# Master_Transmit.net
KiCad netlist of a schematic drawn in Altium Designer
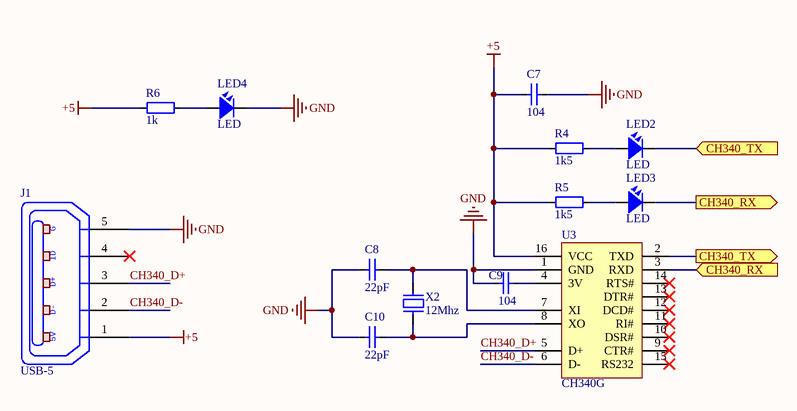
[diagram p0: Master_Transmit.SchDoc]

(export (version "E")
  (design (tool "Eeschema 10.0.6"))
  (components
    (comp (ref "C7")
      (value "104")
      (footprint "CAP_0805")
      (description "Capacitor")
      (fields (field (name "PUBLISHER") "Altium Limited"))
      (libsource (lib "My Library") (part "CapSMD"))
    )
    (comp (ref "C8")
      (value "22pF")
      (footprint "CAP_0805")
      (description "Capacitor")
      (fields (field (name "PUBLISHER") "Altium Limited"))
      (libsource (lib "My Library") (part "CapSMD"))
    )
    (comp (ref "C9")
      (value "104")
      (footprint "CAP_0805")
      (description "Capacitor")
      (fields (field (name "PUBLISHER") "Altium Limited"))
      (libsource (lib "My Library") (part "CapSMD"))
    )
    (comp (ref "C10")
      (value "22pF")
      (footprint "CAP_0805")
      (description "Capacitor")
      (fields (field (name "PUBLISHER") "Altium Limited"))
      (libsource (lib "My Library") (part "CapSMD"))
    )
    (comp (ref "J1")
      (value "USB-5")
      (footprint "USB-M1")
      (fields
        (field (name "MANUFACTURER") "FCI")
        (field (name "MANUFACTURER PART NUMBER") "10118193-0001LF")
        (field (name ".CREATOR") "MM")
        (field (name ".CHECKED PCB") "RF")
        (field (name ".CHECKED SCH") "MM")
      )
      (libsource (lib "My Library") (part "USB-5"))
    )
    (comp (ref "LED2")
      (value "LED")
      (footprint "LED-0805-Green")
      (description "LED Single colour Green and Red")
      (libsource (lib "My Library") (part "LED"))
    )
    (comp (ref "LED3")
      (value "LED")
      (footprint "LED-0805-Blue")
      (description "LED Single colour Green and Red")
      (libsource (lib "My Library") (part "LED"))
    )
    (comp (ref "LED4")
      (value "LED")
      (footprint "LED-0805-Red")
      (description "LED Single colour Green and Red")
      (libsource (lib "My Library") (part "LED"))
    )
    (comp (ref "R4")
      (value "1k5")
      (footprint "RES-SMD-0805")
      (description "Resistor")
      (fields
        (field (name "MANUFACTURER") "Generic Components")
        (field (name "PUBLISHER") "Altium Hobart Technology Centre")
      )
      (libsource (lib "My Library") (part "Resistor - SMD"))
    )
    (comp (ref "R5")
      (value "1k5")
      (footprint "RES-SMD-0805")
      (description "Resistor")
      (fields
        (field (name "MANUFACTURER") "Generic Components")
        (field (name "PUBLISHER") "Altium Hobart Technology Centre")
      )
      (libsource (lib "My Library") (part "Resistor - SMD"))
    )
    (comp (ref "R6")
      (value "1k")
      (footprint "RES-SMD-0805")
      (description "Resistor")
      (fields
        (field (name "MANUFACTURER") "Generic Components")
        (field (name "PUBLISHER") "Altium Hobart Technology Centre")
      )
      (libsource (lib "My Library") (part "Resistor - SMD"))
    )
    (comp (ref "U3")
      (value "CH340G")
      (footprint "SO16")
      (description "High and Low Side Driver")
      (fields (field (name "PUBLISHER") "Altium Limited"))
      (libsource (lib "My Library") (part "CH340G"))
    )
    (comp (ref "X2")
      (value "12Mhz")
      (footprint "XT2")
      (description "Crystal For all Crystal 2pin.")
      (libsource (lib "My Library") (part "XT2"))
    )
  )
  (nets
    (net (code "1") (name "+5") (class "Default")
      (node (ref "C7") (pin "1") (pinfunction "1_1") (pintype "passive"))
      (node (ref "J1") (pin "1") (pinfunction "P1_1") (pintype "passive"))
      (node (ref "R4") (pin "2") (pinfunction "2_2") (pintype "passive"))
      (node (ref "R5") (pin "2") (pinfunction "2_2") (pintype "passive"))
      (node (ref "R6") (pin "2") (pinfunction "2_2") (pintype "passive"))
      (node (ref "U3") (pin "16") (pinfunction "VCC_16") (pintype "passive"))
    )
    (net (code "2") (name "/CH340_D+") (class "Default")
      (node (ref "J1") (pin "3") (pinfunction "P3_3") (pintype "passive"))
      (node (ref "U3") (pin "5") (pinfunction "D+_5") (pintype "passive"))
    )
    (net (code "3") (name "/CH340_D-") (class "Default")
      (node (ref "J1") (pin "2") (pinfunction "P2_2") (pintype "passive"))
      (node (ref "U3") (pin "6") (pinfunction "D-_6") (pintype "passive"))
    )
    (net (code "4") (name "/CH340_RX") (class "Default")
      (node (ref "LED3") (pin "2") (pinfunction "2_2") (pintype "passive"))
      (node (ref "U3") (pin "3") (pinfunction "RXD_3") (pintype "passive"))
    )
    (net (code "5") (name "/CH340_TX") (class "Default")
      (node (ref "LED2") (pin "2") (pinfunction "2_2") (pintype "passive"))
      (node (ref "U3") (pin "2") (pinfunction "TXD_2") (pintype "passive"))
    )
    (net (code "8") (name "GND") (class "Default")
      (node (ref "C10") (pin "1") (pinfunction "1_1") (pintype "passive"))
      (node (ref "C7") (pin "2") (pinfunction "2_2") (pintype "passive"))
      (node (ref "C8") (pin "1") (pinfunction "1_1") (pintype "passive"))
      (node (ref "C9") (pin "1") (pinfunction "1_1") (pintype "passive"))
      (node (ref "J1") (pin "5") (pinfunction "P5_5") (pintype "passive"))
      (node (ref "LED4") (pin "2") (pinfunction "2_2") (pintype "passive"))
      (node (ref "U3") (pin "1") (pinfunction "GND_1") (pintype "passive"))
    )
    (net (code "9") (name "Net-(LED2-Pad1)") (class "Default")
      (node (ref "LED2") (pin "1") (pinfunction "1_1") (pintype "passive"))
      (node (ref "R4") (pin "1") (pinfunction "1_1") (pintype "passive"))
    )
    (net (code "10") (name "Net-(LED3-Pad1)") (class "Default")
      (node (ref "LED3") (pin "1") (pinfunction "1_1") (pintype "passive"))
      (node (ref "R5") (pin "1") (pinfunction "1_1") (pintype "passive"))
    )
    (net (code "11") (name "Net-(LED4-Pad1)") (class "Default")
      (node (ref "LED4") (pin "1") (pinfunction "1_1") (pintype "passive"))
      (node (ref "R6") (pin "1") (pinfunction "1_1") (pintype "passive"))
    )
    (net (code "12") (name "Net-(U3-3V)") (class "Default")
      (node (ref "C9") (pin "2") (pinfunction "2_2") (pintype "passive"))
      (node (ref "U3") (pin "4") (pinfunction "3V_4") (pintype "passive"))
    )
    (net (code "13") (name "Net-(U3-XI)") (class "Default")
      (node (ref "C8") (pin "2") (pinfunction "2_2") (pintype "passive"))
      (node (ref "U3") (pin "7") (pinfunction "XI_7") (pintype "passive"))
      (node (ref "X2") (pin "2") (pinfunction "2_2") (pintype "passive"))
    )
    (net (code "14") (name "Net-(U3-XO)") (class "Default")
      (node (ref "C10") (pin "2") (pinfunction "2_2") (pintype "passive"))
      (node (ref "U3") (pin "8") (pinfunction "XO_8") (pintype "passive"))
      (node (ref "X2") (pin "1") (pinfunction "1_1") (pintype "passive"))
    )
    (net (code "15") (name "unconnected-(J1-P4-Pad4)") (class "Default")
      (node (ref "J1") (pin "4") (pinfunction "P4_4") (pintype "passive+no_connect"))
    )
    (net (code "16") (name "unconnected-(U3-CTR#-Pad9)") (class "Default")
      (node (ref "U3") (pin "9") (pinfunction "CTR#_9") (pintype "passive+no_connect"))
    )
    (net (code "17") (name "unconnected-(U3-DCD#-Pad12)") (class "Default")
      (node (ref "U3") (pin "12") (pinfunction "DCD#_12") (pintype "passive+no_connect"))
    )
    (net (code "18") (name "unconnected-(U3-DSR#-Pad10)") (class "Default")
      (node (ref "U3") (pin "10") (pinfunction "DSR#_10") (pintype "passive+no_connect"))
    )
    (net (code "19") (name "unconnected-(U3-DTR#-Pad13)") (class "Default")
      (node (ref "U3") (pin "13") (pinfunction "DTR#_13") (pintype "passive+no_connect"))
    )
    (net (code "20") (name "unconnected-(U3-RI#-Pad11)") (class "Default")
      (node (ref "U3") (pin "11") (pinfunction "RI#_11") (pintype "passive+no_connect"))
    )
    (net (code "21") (name "unconnected-(U3-RS232-Pad15)") (class "Default")
      (node (ref "U3") (pin "15") (pinfunction "RS232_15") (pintype "passive+no_connect"))
    )
    (net (code "22") (name "unconnected-(U3-RTS#-Pad14)") (class "Default")
      (node (ref "U3") (pin "14") (pinfunction "RTS#_14") (pintype "passive+no_connect"))
    )
  )
)
